# charging-dock-10.net
KiCad netlist of a schematic drawn in EasyEDA Pro
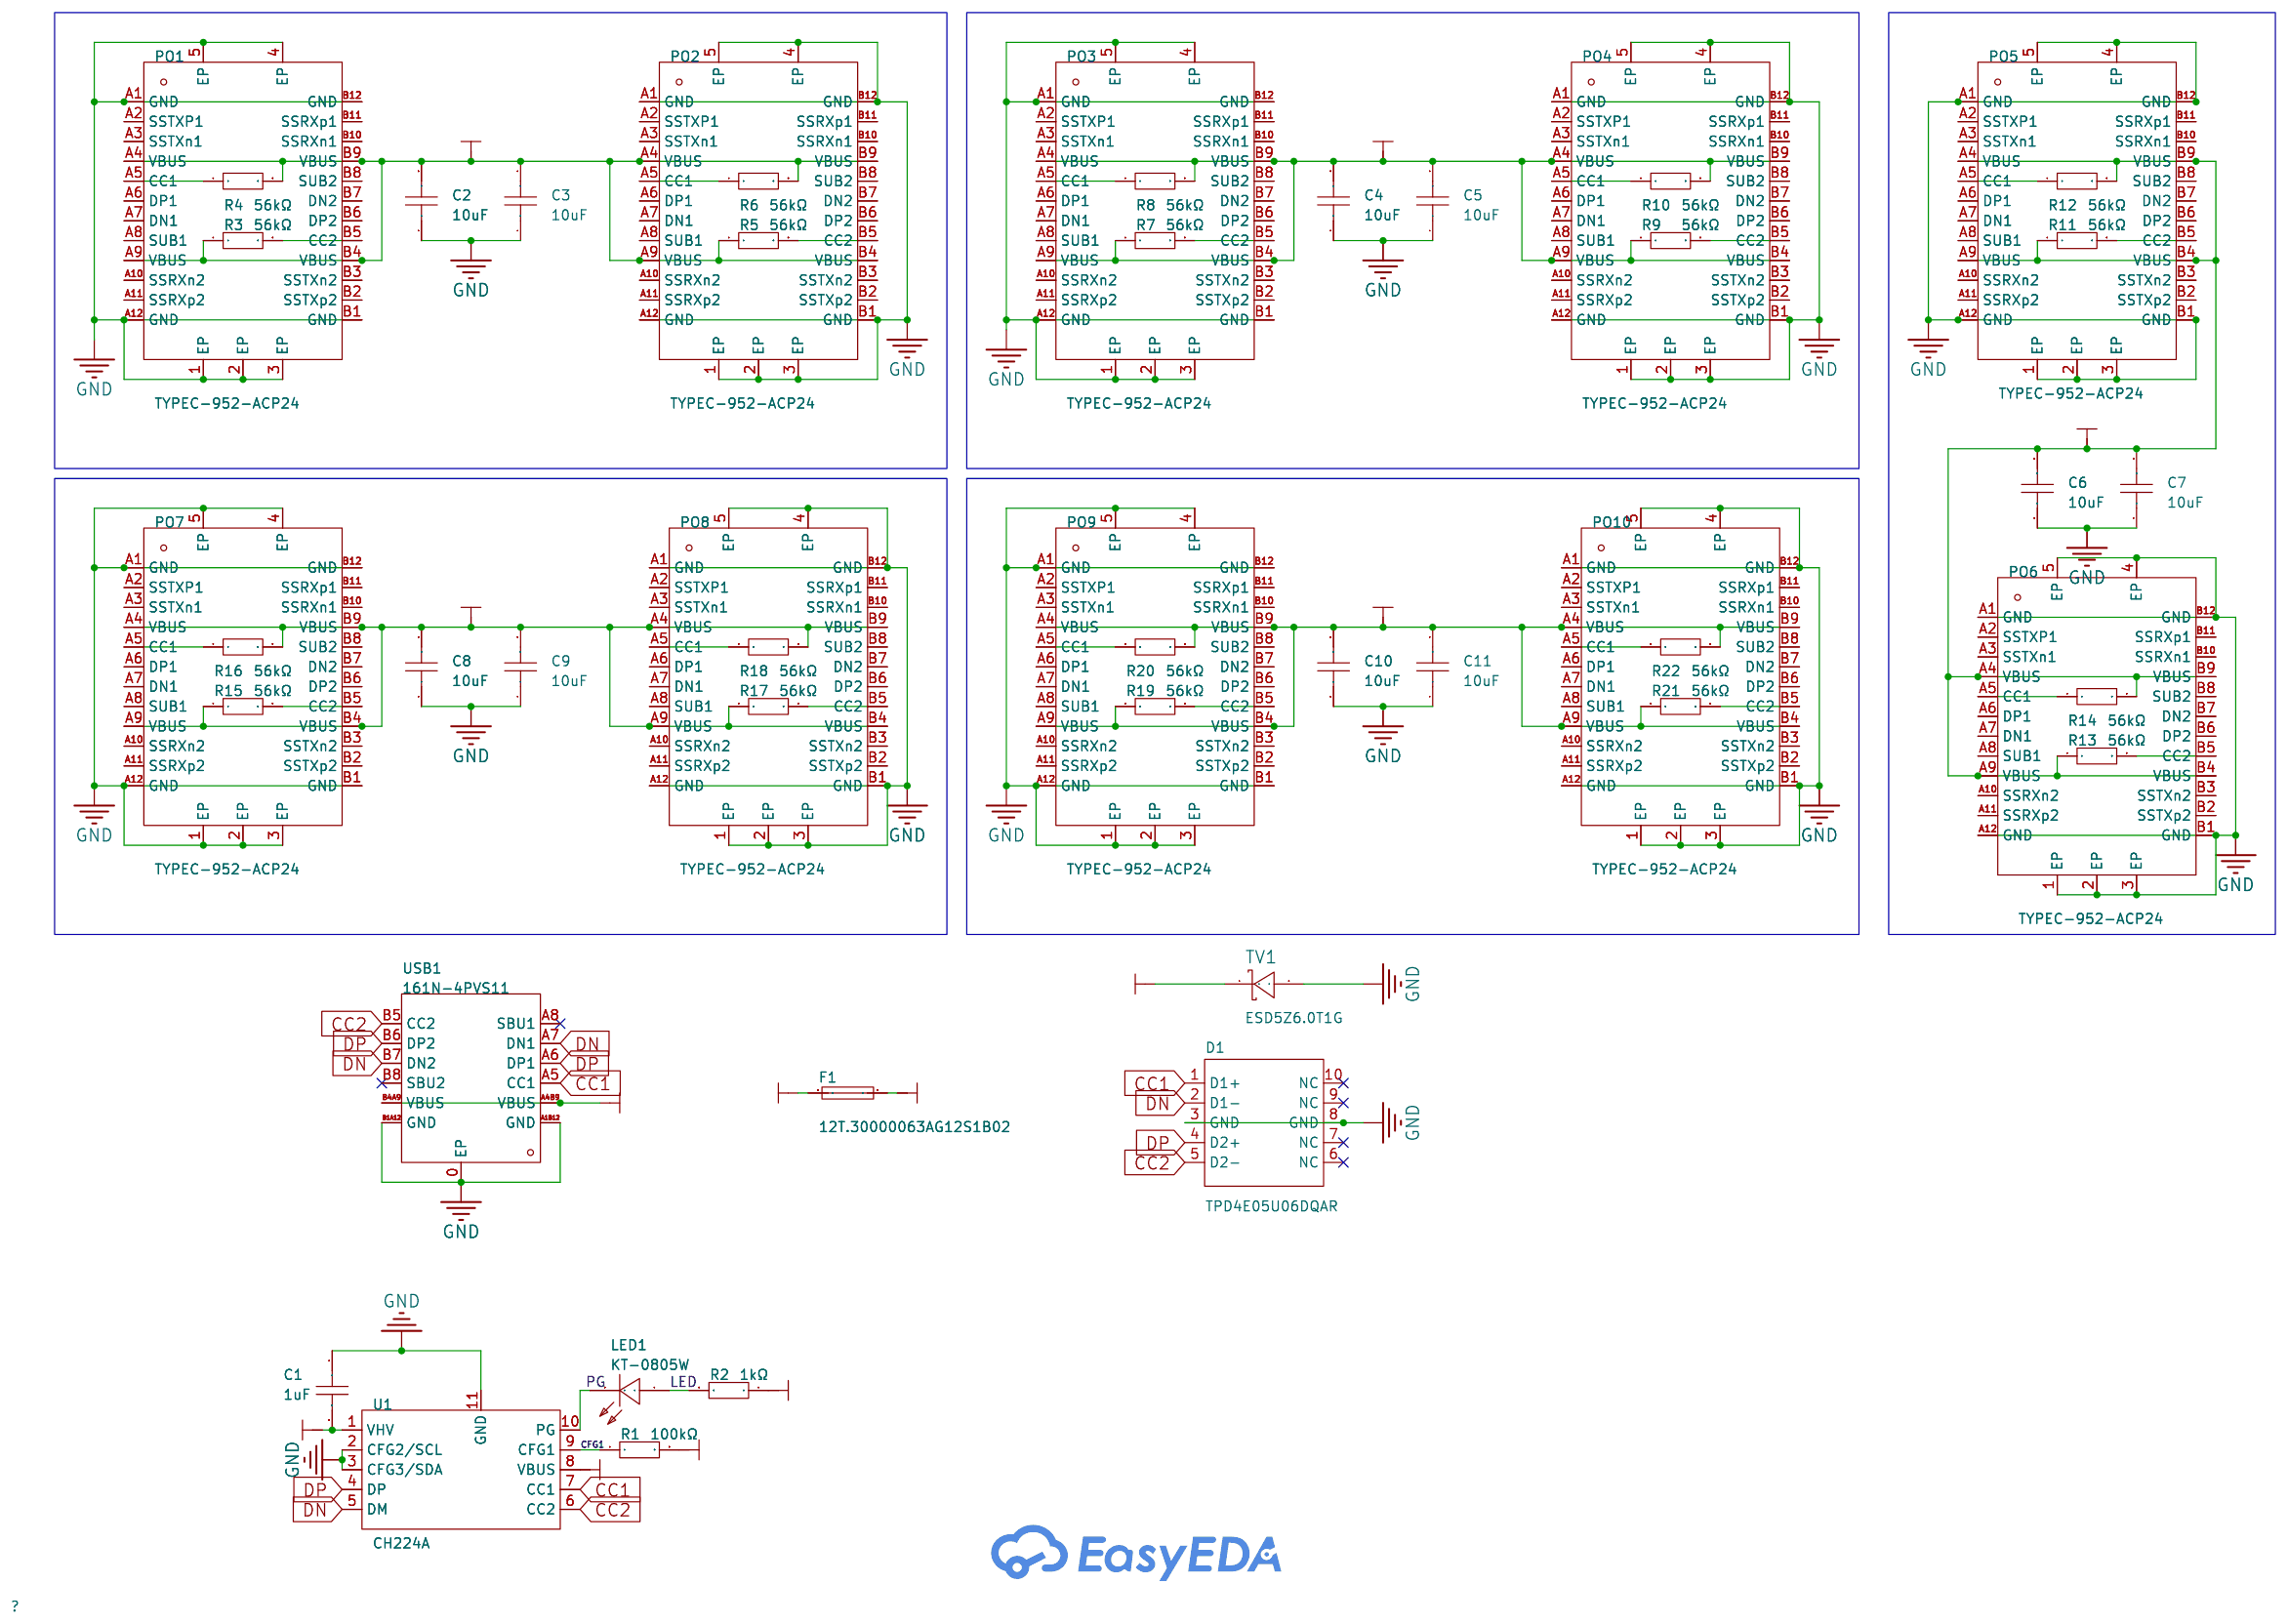
[diagram p0: schematic sheet]

(export (version "E")
  (design (tool "Eeschema 10.0.6"))
  (components
    (comp (ref "C1")
      (value "1uF")
      (footprint "easyedapro:C0603")
      (fields
        (field (name "Manufacturer Part") "CL10A105KB8NNNC")
        (field (name "Manufacturer") "SAMSUNG(三星)")
      )
      (libsource (lib "easyedapro") (part "CL10A105KB8NNNC"))
    )
    (comp (ref "C2")
      (value "10uF")
      (footprint "easyedapro:C0805")
      (fields
        (field (name "Manufacturer Part") "CL21A106KAYNNNE")
        (field (name "Manufacturer") "SAMSUNG(三星)")
      )
      (libsource (lib "easyedapro") (part "CL21A106KAYNNNE"))
    )
    (comp (ref "C3")
      (value "10uF")
      (footprint "easyedapro:C0805")
      (fields
        (field (name "Manufacturer Part") "CL21A106KAYNNNE")
        (field (name "Manufacturer") "SAMSUNG(三星)")
      )
      (libsource (lib "easyedapro") (part "CL21A106KAYNNNE"))
    )
    (comp (ref "C4")
      (value "10uF")
      (footprint "easyedapro:C0805")
      (fields
        (field (name "Manufacturer Part") "CL21A106KAYNNNE")
        (field (name "Manufacturer") "SAMSUNG(三星)")
      )
      (libsource (lib "easyedapro") (part "CL21A106KAYNNNE"))
    )
    (comp (ref "C5")
      (value "10uF")
      (footprint "easyedapro:C0805")
      (fields
        (field (name "Manufacturer Part") "CL21A106KAYNNNE")
        (field (name "Manufacturer") "SAMSUNG(三星)")
      )
      (libsource (lib "easyedapro") (part "CL21A106KAYNNNE"))
    )
    (comp (ref "C6")
      (value "10uF")
      (footprint "easyedapro:C0805")
      (fields
        (field (name "Manufacturer Part") "CL21A106KAYNNNE")
        (field (name "Manufacturer") "SAMSUNG(三星)")
      )
      (libsource (lib "easyedapro") (part "CL21A106KAYNNNE"))
    )
    (comp (ref "C7")
      (value "10uF")
      (footprint "easyedapro:C0805")
      (fields
        (field (name "Manufacturer Part") "CL21A106KAYNNNE")
        (field (name "Manufacturer") "SAMSUNG(三星)")
      )
      (libsource (lib "easyedapro") (part "CL21A106KAYNNNE"))
    )
    (comp (ref "C8")
      (value "10uF")
      (footprint "easyedapro:C0805")
      (fields
        (field (name "Manufacturer Part") "CL21A106KAYNNNE")
        (field (name "Manufacturer") "SAMSUNG(三星)")
      )
      (libsource (lib "easyedapro") (part "CL21A106KAYNNNE"))
    )
    (comp (ref "C9")
      (value "10uF")
      (footprint "easyedapro:C0805")
      (fields
        (field (name "Manufacturer Part") "CL21A106KAYNNNE")
        (field (name "Manufacturer") "SAMSUNG(三星)")
      )
      (libsource (lib "easyedapro") (part "CL21A106KAYNNNE"))
    )
    (comp (ref "C10")
      (value "10uF")
      (footprint "easyedapro:C0805")
      (fields
        (field (name "Manufacturer Part") "CL21A106KAYNNNE")
        (field (name "Manufacturer") "SAMSUNG(三星)")
      )
      (libsource (lib "easyedapro") (part "CL21A106KAYNNNE"))
    )
    (comp (ref "C11")
      (value "10uF")
      (footprint "easyedapro:C0805")
      (fields
        (field (name "Manufacturer Part") "CL21A106KAYNNNE")
        (field (name "Manufacturer") "SAMSUNG(三星)")
      )
      (libsource (lib "easyedapro") (part "CL21A106KAYNNNE"))
    )
    (comp (ref "D1")
      (value "TPD4E05U06DQAR")
      (footprint "easyedapro:USON-10_L2.5-W1.0-P0.50-BL")
      (fields (field (name "Manufacturer") "TI(德州仪器)"))
      (libsource (lib "easyedapro") (part "TPD4E05U06DQAR_C138714"))
    )
    (comp (ref "F1")
      (value "12T.30000063AG12S1B02")
      (footprint "easyedapro:F1206")
      (fields (field (name "Manufacturer") "xcfuse(旭程)"))
      (libsource (lib "easyedapro") (part "3A 63V"))
    )
    (comp (ref "LED1")
      (value "KT-0805W")
      (footprint "easyedapro:LED0805-R-RD")
      (fields (field (name "Manufacturer") "KENTO"))
      (libsource (lib "easyedapro") (part "whiteLEDSMD"))
    )
    (comp (ref "PO1")
      (value "TYPEC-952-ACP24")
      (footprint "easyedapro:USB-C-SMD_TYPEC-952-ACP24-OPENPAW")
      (fields (field (name "Manufacturer") "XUNPU(讯普)"))
      (libsource (lib "easyedapro") (part "TYPEC-952-ACP24"))
    )
    (comp (ref "PO2")
      (value "TYPEC-952-ACP24")
      (footprint "easyedapro:USB-C-SMD_TYPEC-952-ACP24-OPENPAW")
      (fields (field (name "Manufacturer") "XUNPU(讯普)"))
      (libsource (lib "easyedapro") (part "TYPEC-952-ACP24"))
    )
    (comp (ref "PO3")
      (value "TYPEC-952-ACP24")
      (footprint "easyedapro:USB-C-SMD_TYPEC-952-ACP24-OPENPAW")
      (fields (field (name "Manufacturer") "XUNPU(讯普)"))
      (libsource (lib "easyedapro") (part "TYPEC-952-ACP24"))
    )
    (comp (ref "PO4")
      (value "TYPEC-952-ACP24")
      (footprint "easyedapro:USB-C-SMD_TYPEC-952-ACP24-OPENPAW")
      (fields (field (name "Manufacturer") "XUNPU(讯普)"))
      (libsource (lib "easyedapro") (part "TYPEC-952-ACP24"))
    )
    (comp (ref "PO5")
      (value "TYPEC-952-ACP24")
      (footprint "easyedapro:USB-C-SMD_TYPEC-952-ACP24-OPENPAW")
      (fields (field (name "Manufacturer") "XUNPU(讯普)"))
      (libsource (lib "easyedapro") (part "TYPEC-952-ACP24"))
    )
    (comp (ref "PO6")
      (value "TYPEC-952-ACP24")
      (footprint "easyedapro:USB-C-SMD_TYPEC-952-ACP24-OPENPAW")
      (fields (field (name "Manufacturer") "XUNPU(讯普)"))
      (libsource (lib "easyedapro") (part "TYPEC-952-ACP24"))
    )
    (comp (ref "PO7")
      (value "TYPEC-952-ACP24")
      (footprint "easyedapro:USB-C-SMD_TYPEC-952-ACP24-OPENPAW")
      (fields (field (name "Manufacturer") "XUNPU(讯普)"))
      (libsource (lib "easyedapro") (part "TYPEC-952-ACP24"))
    )
    (comp (ref "PO8")
      (value "TYPEC-952-ACP24")
      (footprint "easyedapro:USB-C-SMD_TYPEC-952-ACP24-OPENPAW")
      (fields (field (name "Manufacturer") "XUNPU(讯普)"))
      (libsource (lib "easyedapro") (part "TYPEC-952-ACP24"))
    )
    (comp (ref "PO9")
      (value "TYPEC-952-ACP24")
      (footprint "easyedapro:USB-C-SMD_TYPEC-952-ACP24-OPENPAW")
      (fields (field (name "Manufacturer") "XUNPU(讯普)"))
      (libsource (lib "easyedapro") (part "TYPEC-952-ACP24"))
    )
    (comp (ref "PO10")
      (value "TYPEC-952-ACP24")
      (footprint "easyedapro:USB-C-SMD_TYPEC-952-ACP24-OPENPAW")
      (fields (field (name "Manufacturer") "XUNPU(讯普)"))
      (libsource (lib "easyedapro") (part "TYPEC-952-ACP24"))
    )
    (comp (ref "R1")
      (value "100kΩ")
      (footprint "easyedapro:R0603")
      (fields
        (field (name "Manufacturer Part") "0603WAF1003T5E")
        (field (name "Manufacturer") "UNI-ROYAL(厚声)")
      )
      (libsource (lib "easyedapro") (part "0603WAF1001T5E"))
    )
    (comp (ref "R2")
      (value "1kΩ")
      (footprint "easyedapro:R0603")
      (fields
        (field (name "Manufacturer Part") "0603WAF1001T5E")
        (field (name "Manufacturer") "UNI-ROYAL(厚声)")
      )
      (libsource (lib "easyedapro") (part "0603WAF1001T5E"))
    )
    (comp (ref "R3")
      (value "56kΩ")
      (footprint "easyedapro:R0603")
      (fields
        (field (name "Manufacturer Part") "0603WAF5602T5E")
        (field (name "Manufacturer") "UNI-ROYAL(厚声)")
      )
      (libsource (lib "easyedapro") (part "0603WAF1001T5E"))
    )
    (comp (ref "R4")
      (value "56kΩ")
      (footprint "easyedapro:R0603")
      (fields
        (field (name "Manufacturer Part") "0603WAF5602T5E")
        (field (name "Manufacturer") "UNI-ROYAL(厚声)")
      )
      (libsource (lib "easyedapro") (part "0603WAF1001T5E"))
    )
    (comp (ref "R5")
      (value "56kΩ")
      (footprint "easyedapro:R0603")
      (fields
        (field (name "Manufacturer Part") "0603WAF5602T5E")
        (field (name "Manufacturer") "UNI-ROYAL(厚声)")
      )
      (libsource (lib "easyedapro") (part "0603WAF1001T5E"))
    )
    (comp (ref "R6")
      (value "56kΩ")
      (footprint "easyedapro:R0603")
      (fields
        (field (name "Manufacturer Part") "0603WAF5602T5E")
        (field (name "Manufacturer") "UNI-ROYAL(厚声)")
      )
      (libsource (lib "easyedapro") (part "0603WAF1001T5E"))
    )
    (comp (ref "R7")
      (value "56kΩ")
      (footprint "easyedapro:R0603")
      (fields
        (field (name "Manufacturer Part") "0603WAF5602T5E")
        (field (name "Manufacturer") "UNI-ROYAL(厚声)")
      )
      (libsource (lib "easyedapro") (part "0603WAF1001T5E"))
    )
    (comp (ref "R8")
      (value "56kΩ")
      (footprint "easyedapro:R0603")
      (fields
        (field (name "Manufacturer Part") "0603WAF5602T5E")
        (field (name "Manufacturer") "UNI-ROYAL(厚声)")
      )
      (libsource (lib "easyedapro") (part "0603WAF1001T5E"))
    )
    (comp (ref "R9")
      (value "56kΩ")
      (footprint "easyedapro:R0603")
      (fields
        (field (name "Manufacturer Part") "0603WAF5602T5E")
        (field (name "Manufacturer") "UNI-ROYAL(厚声)")
      )
      (libsource (lib "easyedapro") (part "0603WAF1001T5E"))
    )
    (comp (ref "R10")
      (value "56kΩ")
      (footprint "easyedapro:R0603")
      (fields
        (field (name "Manufacturer Part") "0603WAF5602T5E")
        (field (name "Manufacturer") "UNI-ROYAL(厚声)")
      )
      (libsource (lib "easyedapro") (part "0603WAF1001T5E"))
    )
    (comp (ref "R11")
      (value "56kΩ")
      (footprint "easyedapro:R0603")
      (fields
        (field (name "Manufacturer Part") "0603WAF5602T5E")
        (field (name "Manufacturer") "UNI-ROYAL(厚声)")
      )
      (libsource (lib "easyedapro") (part "0603WAF1001T5E"))
    )
    (comp (ref "R12")
      (value "56kΩ")
      (footprint "easyedapro:R0603")
      (fields
        (field (name "Manufacturer Part") "0603WAF5602T5E")
        (field (name "Manufacturer") "UNI-ROYAL(厚声)")
      )
      (libsource (lib "easyedapro") (part "0603WAF1001T5E"))
    )
    (comp (ref "R13")
      (value "56kΩ")
      (footprint "easyedapro:R0603")
      (fields
        (field (name "Manufacturer Part") "0603WAF5602T5E")
        (field (name "Manufacturer") "UNI-ROYAL(厚声)")
      )
      (libsource (lib "easyedapro") (part "0603WAF1001T5E"))
    )
    (comp (ref "R14")
      (value "56kΩ")
      (footprint "easyedapro:R0603")
      (fields
        (field (name "Manufacturer Part") "0603WAF5602T5E")
        (field (name "Manufacturer") "UNI-ROYAL(厚声)")
      )
      (libsource (lib "easyedapro") (part "0603WAF1001T5E"))
    )
    (comp (ref "R15")
      (value "56kΩ")
      (footprint "easyedapro:R0603")
      (fields
        (field (name "Manufacturer Part") "0603WAF5602T5E")
        (field (name "Manufacturer") "UNI-ROYAL(厚声)")
      )
      (libsource (lib "easyedapro") (part "0603WAF1001T5E"))
    )
    (comp (ref "R16")
      (value "56kΩ")
      (footprint "easyedapro:R0603")
      (fields
        (field (name "Manufacturer Part") "0603WAF5602T5E")
        (field (name "Manufacturer") "UNI-ROYAL(厚声)")
      )
      (libsource (lib "easyedapro") (part "0603WAF1001T5E"))
    )
    (comp (ref "R17")
      (value "56kΩ")
      (footprint "easyedapro:R0603")
      (fields
        (field (name "Manufacturer Part") "0603WAF5602T5E")
        (field (name "Manufacturer") "UNI-ROYAL(厚声)")
      )
      (libsource (lib "easyedapro") (part "0603WAF1001T5E"))
    )
    (comp (ref "R18")
      (value "56kΩ")
      (footprint "easyedapro:R0603")
      (fields
        (field (name "Manufacturer Part") "0603WAF5602T5E")
        (field (name "Manufacturer") "UNI-ROYAL(厚声)")
      )
      (libsource (lib "easyedapro") (part "0603WAF1001T5E"))
    )
    (comp (ref "R19")
      (value "56kΩ")
      (footprint "easyedapro:R0603")
      (fields
        (field (name "Manufacturer Part") "0603WAF5602T5E")
        (field (name "Manufacturer") "UNI-ROYAL(厚声)")
      )
      (libsource (lib "easyedapro") (part "0603WAF1001T5E"))
    )
    (comp (ref "R20")
      (value "56kΩ")
      (footprint "easyedapro:R0603")
      (fields
        (field (name "Manufacturer Part") "0603WAF5602T5E")
        (field (name "Manufacturer") "UNI-ROYAL(厚声)")
      )
      (libsource (lib "easyedapro") (part "0603WAF1001T5E"))
    )
    (comp (ref "R21")
      (value "56kΩ")
      (footprint "easyedapro:R0603")
      (fields
        (field (name "Manufacturer Part") "0603WAF5602T5E")
        (field (name "Manufacturer") "UNI-ROYAL(厚声)")
      )
      (libsource (lib "easyedapro") (part "0603WAF1001T5E"))
    )
    (comp (ref "R22")
      (value "56kΩ")
      (footprint "easyedapro:R0603")
      (fields
        (field (name "Manufacturer Part") "0603WAF5602T5E")
        (field (name "Manufacturer") "UNI-ROYAL(厚声)")
      )
      (libsource (lib "easyedapro") (part "0603WAF1001T5E"))
    )
    (comp (ref "TV1")
      (value "ESD5Z6.0T1G")
      (footprint "easyedapro:SOD-523F_L1.2-W0.8-LS1.7-RD")
      (fields (field (name "Manufacturer") "onsemi(安森美)"))
      (libsource (lib "easyedapro") (part "ESD5Z6.0T1G"))
    )
    (comp (ref "U1")
      (value "CH224A")
      (footprint "easyedapro:ESSOP-10_L4.9-W3.9-P1.0-LS6.0-TL-EP")
      (fields (field (name "Manufacturer") "WCH(南京沁恒)"))
      (libsource (lib "easyedapro") (part "CH224A"))
    )
    (comp (ref "USB1")
      (value "161N-4PVS11")
      (footprint "easyedapro:USB-C-SMD_HANELECTRICITY_161N-4XVS11")
      (fields (field (name "Manufacturer") "HanElectricity(瀚源)"))
      (libsource (lib "easyedapro") (part "161N-4PVS11"))
    )
  )
  (nets
    (net (code "1") (name "/CFG1") (class "Default")
      (node (ref "R1") (pin "1") (pinfunction "1_1") (pintype "input"))
      (node (ref "U1") (pin "9") (pinfunction "CFG1_9") (pintype "unspecified"))
    )
    (net (code "2") (name "/LED") (class "Default")
      (node (ref "LED1") (pin "1") (pinfunction "A_1") (pintype "unspecified"))
      (node (ref "R2") (pin "2") (pinfunction "2_2") (pintype "input"))
    )
    (net (code "3") (name "/PG") (class "Default")
      (node (ref "LED1") (pin "2") (pinfunction "K_2") (pintype "unspecified"))
      (node (ref "U1") (pin "10") (pinfunction "PG_10") (pintype "unspecified"))
    )
    (net (code "4") (name "CC1") (class "Default")
      (node (ref "D1") (pin "1") (pinfunction "D1+_1") (pintype "unspecified"))
      (node (ref "U1") (pin "7") (pinfunction "CC1_7") (pintype "unspecified"))
      (node (ref "USB1") (pin "A5") (pinfunction "CC1_A5") (pintype "unspecified"))
    )
    (net (code "5") (name "CC2") (class "Default")
      (node (ref "D1") (pin "5") (pinfunction "D2-_5") (pintype "unspecified"))
      (node (ref "U1") (pin "6") (pinfunction "CC2_6") (pintype "unspecified"))
      (node (ref "USB1") (pin "B5") (pinfunction "CC2_B5") (pintype "unspecified"))
    )
    (net (code "6") (name "DN") (class "Default")
      (node (ref "D1") (pin "2") (pinfunction "D1-_2") (pintype "unspecified"))
      (node (ref "U1") (pin "5") (pinfunction "DM_5") (pintype "unspecified"))
      (node (ref "USB1") (pin "A7") (pinfunction "DN1_A7") (pintype "unspecified"))
      (node (ref "USB1") (pin "B7") (pinfunction "DN2_B7") (pintype "unspecified"))
    )
    (net (code "7") (name "DP") (class "Default")
      (node (ref "D1") (pin "4") (pinfunction "D2+_4") (pintype "unspecified"))
      (node (ref "U1") (pin "4") (pinfunction "DP_4") (pintype "unspecified"))
      (node (ref "USB1") (pin "A6") (pinfunction "DP1_A6") (pintype "unspecified"))
      (node (ref "USB1") (pin "B6") (pinfunction "DP2_B6") (pintype "unspecified"))
    )
    (net (code "8") (name "GND") (class "Default")
      (node (ref "C1") (pin "1") (pinfunction "1_1") (pintype "unspecified"))
      (node (ref "C10") (pin "1") (pinfunction "1_1") (pintype "unspecified"))
      (node (ref "C11") (pin "1") (pinfunction "1_1") (pintype "unspecified"))
      (node (ref "C2") (pin "1") (pinfunction "1_1") (pintype "unspecified"))
      (node (ref "C3") (pin "1") (pinfunction "1_1") (pintype "unspecified"))
      (node (ref "C4") (pin "1") (pinfunction "1_1") (pintype "unspecified"))
      (node (ref "C5") (pin "1") (pinfunction "1_1") (pintype "unspecified"))
      (node (ref "C6") (pin "1") (pinfunction "1_1") (pintype "unspecified"))
      (node (ref "C7") (pin "1") (pinfunction "1_1") (pintype "unspecified"))
      (node (ref "C8") (pin "1") (pinfunction "1_1") (pintype "unspecified"))
      (node (ref "C9") (pin "1") (pinfunction "1_1") (pintype "unspecified"))
      (node (ref "D1") (pin "3") (pinfunction "GND_3") (pintype "unspecified"))
      (node (ref "D1") (pin "8") (pinfunction "GND_8") (pintype "unspecified"))
      (node (ref "PO1") (pin "1") (pinfunction "EP_1") (pintype "input"))
      (node (ref "PO1") (pin "2") (pinfunction "EP_2") (pintype "input"))
      (node (ref "PO1") (pin "3") (pinfunction "EP_3") (pintype "input"))
      (node (ref "PO1") (pin "4") (pinfunction "EP_4") (pintype "input"))
      (node (ref "PO1") (pin "5") (pinfunction "EP_5") (pintype "input"))
      (node (ref "PO1") (pin "A1") (pinfunction "GND_A1") (pintype "input"))
      (node (ref "PO1") (pin "A12") (pinfunction "GND_A12") (pintype "input"))
      (node (ref "PO1") (pin "B1") (pinfunction "GND_B1") (pintype "input"))
      (node (ref "PO1") (pin "B12") (pinfunction "GND_B12") (pintype "input"))
      (node (ref "PO10") (pin "1") (pinfunction "EP_1") (pintype "input"))
      (node (ref "PO10") (pin "2") (pinfunction "EP_2") (pintype "input"))
      (node (ref "PO10") (pin "3") (pinfunction "EP_3") (pintype "input"))
      (node (ref "PO10") (pin "4") (pinfunction "EP_4") (pintype "input"))
      (node (ref "PO10") (pin "5") (pinfunction "EP_5") (pintype "input"))
      (node (ref "PO10") (pin "A1") (pinfunction "GND_A1") (pintype "input"))
      (node (ref "PO10") (pin "A12") (pinfunction "GND_A12") (pintype "input"))
      (node (ref "PO10") (pin "B1") (pinfunction "GND_B1") (pintype "input"))
      (node (ref "PO10") (pin "B12") (pinfunction "GND_B12") (pintype "input"))
      (node (ref "PO2") (pin "1") (pinfunction "EP_1") (pintype "input"))
      (node (ref "PO2") (pin "2") (pinfunction "EP_2") (pintype "input"))
      (node (ref "PO2") (pin "3") (pinfunction "EP_3") (pintype "input"))
      (node (ref "PO2") (pin "4") (pinfunction "EP_4") (pintype "input"))
      (node (ref "PO2") (pin "5") (pinfunction "EP_5") (pintype "input"))
      (node (ref "PO2") (pin "A1") (pinfunction "GND_A1") (pintype "input"))
      (node (ref "PO2") (pin "A12") (pinfunction "GND_A12") (pintype "input"))
      (node (ref "PO2") (pin "B1") (pinfunction "GND_B1") (pintype "input"))
      (node (ref "PO2") (pin "B12") (pinfunction "GND_B12") (pintype "input"))
      (node (ref "PO3") (pin "1") (pinfunction "EP_1") (pintype "input"))
      (node (ref "PO3") (pin "2") (pinfunction "EP_2") (pintype "input"))
      (node (ref "PO3") (pin "3") (pinfunction "EP_3") (pintype "input"))
      (node (ref "PO3") (pin "4") (pinfunction "EP_4") (pintype "input"))
      (node (ref "PO3") (pin "5") (pinfunction "EP_5") (pintype "input"))
      (node (ref "PO3") (pin "A1") (pinfunction "GND_A1") (pintype "input"))
      (node (ref "PO3") (pin "A12") (pinfunction "GND_A12") (pintype "input"))
      (node (ref "PO3") (pin "B1") (pinfunction "GND_B1") (pintype "input"))
      (node (ref "PO3") (pin "B12") (pinfunction "GND_B12") (pintype "input"))
      (node (ref "PO4") (pin "1") (pinfunction "EP_1") (pintype "input"))
      (node (ref "PO4") (pin "2") (pinfunction "EP_2") (pintype "input"))
      (node (ref "PO4") (pin "3") (pinfunction "EP_3") (pintype "input"))
      (node (ref "PO4") (pin "4") (pinfunction "EP_4") (pintype "input"))
      (node (ref "PO4") (pin "5") (pinfunction "EP_5") (pintype "input"))
      (node (ref "PO4") (pin "A1") (pinfunction "GND_A1") (pintype "input"))
      (node (ref "PO4") (pin "A12") (pinfunction "GND_A12") (pintype "input"))
      (node (ref "PO4") (pin "B1") (pinfunction "GND_B1") (pintype "input"))
      (node (ref "PO4") (pin "B12") (pinfunction "GND_B12") (pintype "input"))
      (node (ref "PO5") (pin "1") (pinfunction "EP_1") (pintype "input"))
      (node (ref "PO5") (pin "2") (pinfunction "EP_2") (pintype "input"))
      (node (ref "PO5") (pin "3") (pinfunction "EP_3") (pintype "input"))
      (node (ref "PO5") (pin "4") (pinfunction "EP_4") (pintype "input"))
      (node (ref "PO5") (pin "5") (pinfunction "EP_5") (pintype "input"))
      (node (ref "PO5") (pin "A1") (pinfunction "GND_A1") (pintype "input"))
      (node (ref "PO5") (pin "A12") (pinfunction "GND_A12") (pintype "input"))
      (node (ref "PO5") (pin "B1") (pinfunction "GND_B1") (pintype "input"))
      (node (ref "PO5") (pin "B12") (pinfunction "GND_B12") (pintype "input"))
      (node (ref "PO6") (pin "1") (pinfunction "EP_1") (pintype "input"))
      (node (ref "PO6") (pin "2") (pinfunction "EP_2") (pintype "input"))
      (node (ref "PO6") (pin "3") (pinfunction "EP_3") (pintype "input"))
      (node (ref "PO6") (pin "4") (pinfunction "EP_4") (pintype "input"))
      (node (ref "PO6") (pin "5") (pinfunction "EP_5") (pintype "input"))
      (node (ref "PO6") (pin "A1") (pinfunction "GND_A1") (pintype "input"))
      (node (ref "PO6") (pin "A12") (pinfunction "GND_A12") (pintype "input"))
      (node (ref "PO6") (pin "B1") (pinfunction "GND_B1") (pintype "input"))
      (node (ref "PO6") (pin "B12") (pinfunction "GND_B12") (pintype "input"))
      (node (ref "PO7") (pin "1") (pinfunction "EP_1") (pintype "input"))
      (node (ref "PO7") (pin "2") (pinfunction "EP_2") (pintype "input"))
      (node (ref "PO7") (pin "3") (pinfunction "EP_3") (pintype "input"))
      (node (ref "PO7") (pin "4") (pinfunction "EP_4") (pintype "input"))
      (node (ref "PO7") (pin "5") (pinfunction "EP_5") (pintype "input"))
      (node (ref "PO7") (pin "A1") (pinfunction "GND_A1") (pintype "input"))
      (node (ref "PO7") (pin "A12") (pinfunction "GND_A12") (pintype "input"))
      (node (ref "PO7") (pin "B1") (pinfunction "GND_B1") (pintype "input"))
      (node (ref "PO7") (pin "B12") (pinfunction "GND_B12") (pintype "input"))
      (node (ref "PO8") (pin "1") (pinfunction "EP_1") (pintype "input"))
      (node (ref "PO8") (pin "2") (pinfunction "EP_2") (pintype "input"))
      (node (ref "PO8") (pin "3") (pinfunction "EP_3") (pintype "input"))
      (node (ref "PO8") (pin "4") (pinfunction "EP_4") (pintype "input"))
      (node (ref "PO8") (pin "5") (pinfunction "EP_5") (pintype "input"))
      (node (ref "PO8") (pin "A1") (pinfunction "GND_A1") (pintype "input"))
      (node (ref "PO8") (pin "A12") (pinfunction "GND_A12") (pintype "input"))
      (node (ref "PO8") (pin "B1") (pinfunction "GND_B1") (pintype "input"))
      (node (ref "PO8") (pin "B12") (pinfunction "GND_B12") (pintype "input"))
      (node (ref "PO9") (pin "1") (pinfunction "EP_1") (pintype "input"))
      (node (ref "PO9") (pin "2") (pinfunction "EP_2") (pintype "input"))
      (node (ref "PO9") (pin "3") (pinfunction "EP_3") (pintype "input"))
      (node (ref "PO9") (pin "4") (pinfunction "EP_4") (pintype "input"))
      (node (ref "PO9") (pin "5") (pinfunction "EP_5") (pintype "input"))
      (node (ref "PO9") (pin "A1") (pinfunction "GND_A1") (pintype "input"))
      (node (ref "PO9") (pin "A12") (pinfunction "GND_A12") (pintype "input"))
      (node (ref "PO9") (pin "B1") (pinfunction "GND_B1") (pintype "input"))
      (node (ref "PO9") (pin "B12") (pinfunction "GND_B12") (pintype "input"))
      (node (ref "TV1") (pin "2") (pinfunction "A_2") (pintype "input"))
      (node (ref "U1") (pin "11") (pinfunction "GND_11") (pintype "unspecified"))
      (node (ref "U1") (pin "2") (pinfunction "CFG2/SCL_2") (pintype "unspecified"))
      (node (ref "U1") (pin "3") (pinfunction "CFG3/SDA_3") (pintype "unspecified"))
      (node (ref "USB1") (pin "0") (pinfunction "EP_0") (pintype "unspecified"))
      (node (ref "USB1") (pin "A1B12") (pinfunction "GND_A1B12") (pintype "unspecified"))
      (node (ref "USB1") (pin "B1A12") (pinfunction "GND_B1A12") (pintype "unspecified"))
    )
    (net (code "9") (name "Net-(PO1-CC1)") (class "Default")
      (node (ref "PO1") (pin "A5") (pinfunction "CC1_A5") (pintype "input"))
      (node (ref "R4") (pin "1") (pinfunction "1_1") (pintype "input"))
    )
    (net (code "10") (name "Net-(PO1-CC2)") (class "Default")
      (node (ref "PO1") (pin "B5") (pinfunction "CC2_B5") (pintype "input"))
      (node (ref "R3") (pin "2") (pinfunction "2_2") (pintype "input"))
    )
    (net (code "11") (name "Net-(PO2-CC1)") (class "Default")
      (node (ref "PO2") (pin "A5") (pinfunction "CC1_A5") (pintype "input"))
      (node (ref "R6") (pin "1") (pinfunction "1_1") (pintype "input"))
    )
    (net (code "12") (name "Net-(PO2-CC2)") (class "Default")
      (node (ref "PO2") (pin "B5") (pinfunction "CC2_B5") (pintype "input"))
      (node (ref "R5") (pin "2") (pinfunction "2_2") (pintype "input"))
    )
    (net (code "13") (name "Net-(PO3-CC1)") (class "Default")
      (node (ref "PO3") (pin "A5") (pinfunction "CC1_A5") (pintype "input"))
      (node (ref "R8") (pin "1") (pinfunction "1_1") (pintype "input"))
    )
    (net (code "14") (name "Net-(PO3-CC2)") (class "Default")
      (node (ref "PO3") (pin "B5") (pinfunction "CC2_B5") (pintype "input"))
      (node (ref "R7") (pin "2") (pinfunction "2_2") (pintype "input"))
    )
    (net (code "15") (name "Net-(PO4-CC1)") (class "Default")
      (node (ref "PO4") (pin "A5") (pinfunction "CC1_A5") (pintype "input"))
      (node (ref "R10") (pin "1") (pinfunction "1_1") (pintype "input"))
    )
    (net (code "16") (name "Net-(PO4-CC2)") (class "Default")
      (node (ref "PO4") (pin "B5") (pinfunction "CC2_B5") (pintype "input"))
      (node (ref "R9") (pin "2") (pinfunction "2_2") (pintype "input"))
    )
    (net (code "17") (name "Net-(PO5-CC1)") (class "Default")
      (node (ref "PO5") (pin "A5") (pinfunction "CC1_A5") (pintype "input"))
      (node (ref "R12") (pin "1") (pinfunction "1_1") (pintype "input"))
    )
    (net (code "18") (name "Net-(PO5-CC2)") (class "Default")
      (node (ref "PO5") (pin "B5") (pinfunction "CC2_B5") (pintype "input"))
      (node (ref "R11") (pin "2") (pinfunction "2_2") (pintype "input"))
    )
    (net (code "19") (name "Net-(PO6-CC1)") (class "Default")
      (node (ref "PO6") (pin "A5") (pinfunction "CC1_A5") (pintype "input"))
      (node (ref "R14") (pin "1") (pinfunction "1_1") (pintype "input"))
    )
    (net (code "20") (name "Net-(PO6-CC2)") (class "Default")
      (node (ref "PO6") (pin "B5") (pinfunction "CC2_B5") (pintype "input"))
      (node (ref "R13") (pin "2") (pinfunction "2_2") (pintype "input"))
    )
    (net (code "21") (name "Net-(PO7-CC1)") (class "Default")
      (node (ref "PO7") (pin "A5") (pinfunction "CC1_A5") (pintype "input"))
      (node (ref "R16") (pin "1") (pinfunction "1_1") (pintype "input"))
    )
    (net (code "22") (name "Net-(PO7-CC2)") (class "Default")
      (node (ref "PO7") (pin "B5") (pinfunction "CC2_B5") (pintype "input"))
      (node (ref "R15") (pin "2") (pinfunction "2_2") (pintype "input"))
    )
    (net (code "23") (name "Net-(PO8-CC1)") (class "Default")
      (node (ref "PO8") (pin "A5") (pinfunction "CC1_A5") (pintype "input"))
      (node (ref "R18") (pin "1") (pinfunction "1_1") (pintype "input"))
    )
    (net (code "24") (name "Net-(PO8-CC2)") (class "Default")
      (node (ref "PO8") (pin "B5") (pinfunction "CC2_B5") (pintype "input"))
      (node (ref "R17") (pin "2") (pinfunction "2_2") (pintype "input"))
    )
    (net (code "25") (name "Net-(PO9-CC1)") (class "Default")
      (node (ref "PO9") (pin "A5") (pinfunction "CC1_A5") (pintype "input"))
      (node (ref "R20") (pin "1") (pinfunction "1_1") (pintype "input"))
    )
    (net (code "26") (name "Net-(PO9-CC2)") (class "Default")
      (node (ref "PO9") (pin "B5") (pinfunction "CC2_B5") (pintype "input"))
      (node (ref "R19") (pin "2") (pinfunction "2_2") (pintype "input"))
    )
    (net (code "27") (name "Net-(PO10-CC1)") (class "Default")
      (node (ref "PO10") (pin "A5") (pinfunction "CC1_A5") (pintype "input"))
      (node (ref "R22") (pin "1") (pinfunction "1_1") (pintype "input"))
    )
    (net (code "28") (name "Net-(PO10-CC2)") (class "Default")
      (node (ref "PO10") (pin "B5") (pinfunction "CC2_B5") (pintype "input"))
      (node (ref "R21") (pin "2") (pinfunction "2_2") (pintype "input"))
    )
    (net (code "29") (name "PVBUS") (class "Default")
      (node (ref "C1") (pin "2") (pinfunction "2_2") (pintype "unspecified"))
      (node (ref "C10") (pin "2") (pinfunction "2_2") (pintype "unspecified"))
      (node (ref "C11") (pin "2") (pinfunction "2_2") (pintype "unspecified"))
      (node (ref "C2") (pin "2") (pinfunction "2_2") (pintype "unspecified"))
      (node (ref "C3") (pin "2") (pinfunction "2_2") (pintype "unspecified"))
      (node (ref "C4") (pin "2") (pinfunction "2_2") (pintype "unspecified"))
      (node (ref "C5") (pin "2") (pinfunction "2_2") (pintype "unspecified"))
      (node (ref "C6") (pin "2") (pinfunction "2_2") (pintype "unspecified"))
      (node (ref "C7") (pin "2") (pinfunction "2_2") (pintype "unspecified"))
      (node (ref "C8") (pin "2") (pinfunction "2_2") (pintype "unspecified"))
      (node (ref "C9") (pin "2") (pinfunction "2_2") (pintype "unspecified"))
      (node (ref "F1") (pin "1") (pinfunction "1_1") (pintype "unspecified"))
      (node (ref "PO1") (pin "A4") (pinfunction "VBUS_A4") (pintype "input"))
      (node (ref "PO1") (pin "A9") (pinfunction "VBUS_A9") (pintype "input"))
      (node (ref "PO1") (pin "B4") (pinfunction "VBUS_B4") (pintype "input"))
      (node (ref "PO1") (pin "B9") (pinfunction "VBUS_B9") (pintype "input"))
      (node (ref "PO10") (pin "A4") (pinfunction "VBUS_A4") (pintype "input"))
      (node (ref "PO10") (pin "A9") (pinfunction "VBUS_A9") (pintype "input"))
      (node (ref "PO10") (pin "B4") (pinfunction "VBUS_B4") (pintype "input"))
      (node (ref "PO10") (pin "B9") (pinfunction "VBUS_B9") (pintype "input"))
      (node (ref "PO2") (pin "A4") (pinfunction "VBUS_A4") (pintype "input"))
      (node (ref "PO2") (pin "A9") (pinfunction "VBUS_A9") (pintype "input"))
      (node (ref "PO2") (pin "B4") (pinfunction "VBUS_B4") (pintype "input"))
      (node (ref "PO2") (pin "B9") (pinfunction "VBUS_B9") (pintype "input"))
      (node (ref "PO3") (pin "A4") (pinfunction "VBUS_A4") (pintype "input"))
      (node (ref "PO3") (pin "A9") (pinfunction "VBUS_A9") (pintype "input"))
      (node (ref "PO3") (pin "B4") (pinfunction "VBUS_B4") (pintype "input"))
      (node (ref "PO3") (pin "B9") (pinfunction "VBUS_B9") (pintype "input"))
      (node (ref "PO4") (pin "A4") (pinfunction "VBUS_A4") (pintype "input"))
      (node (ref "PO4") (pin "A9") (pinfunction "VBUS_A9") (pintype "input"))
      (node (ref "PO4") (pin "B4") (pinfunction "VBUS_B4") (pintype "input"))
      (node (ref "PO4") (pin "B9") (pinfunction "VBUS_B9") (pintype "input"))
      (node (ref "PO5") (pin "A4") (pinfunction "VBUS_A4") (pintype "input"))
      (node (ref "PO5") (pin "A9") (pinfunction "VBUS_A9") (pintype "input"))
      (node (ref "PO5") (pin "B4") (pinfunction "VBUS_B4") (pintype "input"))
      (node (ref "PO5") (pin "B9") (pinfunction "VBUS_B9") (pintype "input"))
      (node (ref "PO6") (pin "A4") (pinfunction "VBUS_A4") (pintype "input"))
      (node (ref "PO6") (pin "A9") (pinfunction "VBUS_A9") (pintype "input"))
      (node (ref "PO6") (pin "B4") (pinfunction "VBUS_B4") (pintype "input"))
      (node (ref "PO6") (pin "B9") (pinfunction "VBUS_B9") (pintype "input"))
      (node (ref "PO7") (pin "A4") (pinfunction "VBUS_A4") (pintype "input"))
      (node (ref "PO7") (pin "A9") (pinfunction "VBUS_A9") (pintype "input"))
      (node (ref "PO7") (pin "B4") (pinfunction "VBUS_B4") (pintype "input"))
      (node (ref "PO7") (pin "B9") (pinfunction "VBUS_B9") (pintype "input"))
      (node (ref "PO8") (pin "A4") (pinfunction "VBUS_A4") (pintype "input"))
      (node (ref "PO8") (pin "A9") (pinfunction "VBUS_A9") (pintype "input"))
      (node (ref "PO8") (pin "B4") (pinfunction "VBUS_B4") (pintype "input"))
      (node (ref "PO8") (pin "B9") (pinfunction "VBUS_B9") (pintype "input"))
      (node (ref "PO9") (pin "A4") (pinfunction "VBUS_A4") (pintype "input"))
      (node (ref "PO9") (pin "A9") (pinfunction "VBUS_A9") (pintype "input"))
      (node (ref "PO9") (pin "B4") (pinfunction "VBUS_B4") (pintype "input"))
      (node (ref "PO9") (pin "B9") (pinfunction "VBUS_B9") (pintype "input"))
      (node (ref "R1") (pin "2") (pinfunction "2_2") (pintype "input"))
      (node (ref "R10") (pin "2") (pinfunction "2_2") (pintype "input"))
      (node (ref "R11") (pin "1") (pinfunction "1_1") (pintype "input"))
      (node (ref "R12") (pin "2") (pinfunction "2_2") (pintype "input"))
      (node (ref "R13") (pin "1") (pinfunction "1_1") (pintype "input"))
      (node (ref "R14") (pin "2") (pinfunction "2_2") (pintype "input"))
      (node (ref "R15") (pin "1") (pinfunction "1_1") (pintype "input"))
      (node (ref "R16") (pin "2") (pinfunction "2_2") (pintype "input"))
      (node (ref "R17") (pin "1") (pinfunction "1_1") (pintype "input"))
      (node (ref "R18") (pin "2") (pinfunction "2_2") (pintype "input"))
      (node (ref "R19") (pin "1") (pinfunction "1_1") (pintype "input"))
      (node (ref "R2") (pin "1") (pinfunction "1_1") (pintype "input"))
      (node (ref "R20") (pin "2") (pinfunction "2_2") (pintype "input"))
      (node (ref "R21") (pin "1") (pinfunction "1_1") (pintype "input"))
      (node (ref "R22") (pin "2") (pinfunction "2_2") (pintype "input"))
      (node (ref "R3") (pin "1") (pinfunction "1_1") (pintype "input"))
      (node (ref "R4") (pin "2") (pinfunction "2_2") (pintype "input"))
      (node (ref "R5") (pin "1") (pinfunction "1_1") (pintype "input"))
      (node (ref "R6") (pin "2") (pinfunction "2_2") (pintype "input"))
      (node (ref "R7") (pin "1") (pinfunction "1_1") (pintype "input"))
      (node (ref "R8") (pin "2") (pinfunction "2_2") (pintype "input"))
      (node (ref "R9") (pin "1") (pinfunction "1_1") (pintype "input"))
      (node (ref "TV1") (pin "1") (pinfunction "K_1") (pintype "input"))
      (node (ref "U1") (pin "1") (pinfunction "VHV_1") (pintype "unspecified"))
      (node (ref "U1") (pin "8") (pinfunction "VBUS_8") (pintype "unspecified"))
    )
    (net (code "30") (name "VBUS") (class "Default")
      (node (ref "F1") (pin "2") (pinfunction "2_2") (pintype "unspecified"))
      (node (ref "USB1") (pin "A4B9") (pinfunction "VBUS_A4B9") (pintype "unspecified"))
      (node (ref "USB1") (pin "B4A9") (pinfunction "VBUS_B4A9") (pintype "unspecified"))
    )
    (net (code "31") (name "unconnected-(D1-NC-Pad6)") (class "Default")
      (node (ref "D1") (pin "6") (pinfunction "NC_6") (pintype "unspecified+no_connect"))
    )
    (net (code "32") (name "unconnected-(D1-NC-Pad7)") (class "Default")
      (node (ref "D1") (pin "7") (pinfunction "NC_7") (pintype "unspecified+no_connect"))
    )
    (net (code "33") (name "unconnected-(D1-NC-Pad9)") (class "Default")
      (node (ref "D1") (pin "9") (pinfunction "NC_9") (pintype "unspecified+no_connect"))
    )
    (net (code "34") (name "unconnected-(D1-NC-Pad10)") (class "Default")
      (node (ref "D1") (pin "10") (pinfunction "NC_10") (pintype "unspecified+no_connect"))
    )
    (net (code "35") (name "unconnected-(PO1-DN1-PadA7)") (class "Default")
      (node (ref "PO1") (pin "A7") (pinfunction "DN1_A7") (pintype "input"))
    )
    (net (code "36") (name "unconnected-(PO1-DN2-PadB7)") (class "Default")
      (node (ref "PO1") (pin "B7") (pinfunction "DN2_B7") (pintype "input"))
    )
    (net (code "37") (name "unconnected-(PO1-DP1-PadA6)") (class "Default")
      (node (ref "PO1") (pin "A6") (pinfunction "DP1_A6") (pintype "input"))
    )
    (net (code "38") (name "unconnected-(PO1-DP2-PadB6)") (class "Default")
      (node (ref "PO1") (pin "B6") (pinfunction "DP2_B6") (pintype "input"))
    )
    (net (code "39") (name "unconnected-(PO1-SSRXn1-PadB10)") (class "Default")
      (node (ref "PO1") (pin "B10") (pinfunction "SSRXn1_B10") (pintype "input"))
    )
    (net (code "40") (name "unconnected-(PO1-SSRXn2-PadA10)") (class "Default")
      (node (ref "PO1") (pin "A10") (pinfunction "SSRXn2_A10") (pintype "input"))
    )
    (net (code "41") (name "unconnected-(PO1-SSRXp1-PadB11)") (class "Default")
      (node (ref "PO1") (pin "B11") (pinfunction "SSRXp1_B11") (pintype "input"))
    )
    (net (code "42") (name "unconnected-(PO1-SSRXp2-PadA11)") (class "Default")
      (node (ref "PO1") (pin "A11") (pinfunction "SSRXp2_A11") (pintype "input"))
    )
    (net (code "43") (name "unconnected-(PO1-SSTXP1-PadA2)") (class "Default")
      (node (ref "PO1") (pin "A2") (pinfunction "SSTXP1_A2") (pintype "input"))
    )
    (net (code "44") (name "unconnected-(PO1-SSTXn1-PadA3)") (class "Default")
      (node (ref "PO1") (pin "A3") (pinfunction "SSTXn1_A3") (pintype "input"))
    )
    (net (code "45") (name "unconnected-(PO1-SSTXn2-PadB3)") (class "Default")
      (node (ref "PO1") (pin "B3") (pinfunction "SSTXn2_B3") (pintype "input"))
    )
    (net (code "46") (name "unconnected-(PO1-SSTXp2-PadB2)") (class "Default")
      (node (ref "PO1") (pin "B2") (pinfunction "SSTXp2_B2") (pintype "input"))
    )
    (net (code "47") (name "unconnected-(PO1-SUB1-PadA8)") (class "Default")
      (node (ref "PO1") (pin "A8") (pinfunction "SUB1_A8") (pintype "input"))
    )
    (net (code "48") (name "unconnected-(PO1-SUB2-PadB8)") (class "Default")
      (node (ref "PO1") (pin "B8") (pinfunction "SUB2_B8") (pintype "input"))
    )
    (net (code "49") (name "unconnected-(PO2-DN1-PadA7)") (class "Default")
      (node (ref "PO2") (pin "A7") (pinfunction "DN1_A7") (pintype "input"))
    )
    (net (code "50") (name "unconnected-(PO2-DN2-PadB7)") (class "Default")
      (node (ref "PO2") (pin "B7") (pinfunction "DN2_B7") (pintype "input"))
    )
    (net (code "51") (name "unconnected-(PO2-DP1-PadA6)") (class "Default")
      (node (ref "PO2") (pin "A6") (pinfunction "DP1_A6") (pintype "input"))
    )
    (net (code "52") (name "unconnected-(PO2-DP2-PadB6)") (class "Default")
      (node (ref "PO2") (pin "B6") (pinfunction "DP2_B6") (pintype "input"))
    )
    (net (code "53") (name "unconnected-(PO2-SSRXn1-PadB10)") (class "Default")
      (node (ref "PO2") (pin "B10") (pinfunction "SSRXn1_B10") (pintype "input"))
    )
    (net (code "54") (name "unconnected-(PO2-SSRXn2-PadA10)") (class "Default")
      (node (ref "PO2") (pin "A10") (pinfunction "SSRXn2_A10") (pintype "input"))
    )
    (net (code "55") (name "unconnected-(PO2-SSRXp1-PadB11)") (class "Default")
      (node (ref "PO2") (pin "B11") (pinfunction "SSRXp1_B11") (pintype "input"))
    )
    (net (code "56") (name "unconnected-(PO2-SSRXp2-PadA11)") (class "Default")
      (node (ref "PO2") (pin "A11") (pinfunction "SSRXp2_A11") (pintype "input"))
    )
    (net (code "57") (name "unconnected-(PO2-SSTXP1-PadA2)") (class "Default")
      (node (ref "PO2") (pin "A2") (pinfunction "SSTXP1_A2") (pintype "input"))
    )
    (net (code "58") (name "unconnected-(PO2-SSTXn1-PadA3)") (class "Default")
      (node (ref "PO2") (pin "A3") (pinfunction "SSTXn1_A3") (pintype "input"))
    )
    (net (code "59") (name "unconnected-(PO2-SSTXn2-PadB3)") (class "Default")
      (node (ref "PO2") (pin "B3") (pinfunction "SSTXn2_B3") (pintype "input"))
    )
    (net (code "60") (name "unconnected-(PO2-SSTXp2-PadB2)") (class "Default")
      (node (ref "PO2") (pin "B2") (pinfunction "SSTXp2_B2") (pintype "input"))
    )
    (net (code "61") (name "unconnected-(PO2-SUB1-PadA8)") (class "Default")
      (node (ref "PO2") (pin "A8") (pinfunction "SUB1_A8") (pintype "input"))
    )
    (net (code "62") (name "unconnected-(PO2-SUB2-PadB8)") (class "Default")
      (node (ref "PO2") (pin "B8") (pinfunction "SUB2_B8") (pintype "input"))
    )
    (net (code "63") (name "unconnected-(PO3-DN1-PadA7)") (class "Default")
      (node (ref "PO3") (pin "A7") (pinfunction "DN1_A7") (pintype "input"))
    )
    (net (code "64") (name "unconnected-(PO3-DN2-PadB7)") (class "Default")
      (node (ref "PO3") (pin "B7") (pinfunction "DN2_B7") (pintype "input"))
    )
    (net (code "65") (name "unconnected-(PO3-DP1-PadA6)") (class "Default")
      (node (ref "PO3") (pin "A6") (pinfunction "DP1_A6") (pintype "input"))
    )
    (net (code "66") (name "unconnected-(PO3-DP2-PadB6)") (class "Default")
      (node (ref "PO3") (pin "B6") (pinfunction "DP2_B6") (pintype "input"))
    )
    (net (code "67") (name "unconnected-(PO3-SSRXn1-PadB10)") (class "Default")
      (node (ref "PO3") (pin "B10") (pinfunction "SSRXn1_B10") (pintype "input"))
    )
    (net (code "68") (name "unconnected-(PO3-SSRXn2-PadA10)") (class "Default")
      (node (ref "PO3") (pin "A10") (pinfunction "SSRXn2_A10") (pintype "input"))
    )
    (net (code "69") (name "unconnected-(PO3-SSRXp1-PadB11)") (class "Default")
      (node (ref "PO3") (pin "B11") (pinfunction "SSRXp1_B11") (pintype "input"))
    )
    (net (code "70") (name "unconnected-(PO3-SSRXp2-PadA11)") (class "Default")
      (node (ref "PO3") (pin "A11") (pinfunction "SSRXp2_A11") (pintype "input"))
    )
    (net (code "71") (name "unconnected-(PO3-SSTXP1-PadA2)") (class "Default")
      (node (ref "PO3") (pin "A2") (pinfunction "SSTXP1_A2") (pintype "input"))
    )
    (net (code "72") (name "unconnected-(PO3-SSTXn1-PadA3)") (class "Default")
      (node (ref "PO3") (pin "A3") (pinfunction "SSTXn1_A3") (pintype "input"))
    )
    (net (code "73") (name "unconnected-(PO3-SSTXn2-PadB3)") (class "Default")
      (node (ref "PO3") (pin "B3") (pinfunction "SSTXn2_B3") (pintype "input"))
    )
    (net (code "74") (name "unconnected-(PO3-SSTXp2-PadB2)") (class "Default")
      (node (ref "PO3") (pin "B2") (pinfunction "SSTXp2_B2") (pintype "input"))
    )
    (net (code "75") (name "unconnected-(PO3-SUB1-PadA8)") (class "Default")
      (node (ref "PO3") (pin "A8") (pinfunction "SUB1_A8") (pintype "input"))
    )
    (net (code "76") (name "unconnected-(PO3-SUB2-PadB8)") (class "Default")
      (node (ref "PO3") (pin "B8") (pinfunction "SUB2_B8") (pintype "input"))
    )
    (net (code "77") (name "unconnected-(PO4-DN1-PadA7)") (class "Default")
      (node (ref "PO4") (pin "A7") (pinfunction "DN1_A7") (pintype "input"))
    )
    (net (code "78") (name "unconnected-(PO4-DN2-PadB7)") (class "Default")
      (node (ref "PO4") (pin "B7") (pinfunction "DN2_B7") (pintype "input"))
    )
    (net (code "79") (name "unconnected-(PO4-DP1-PadA6)") (class "Default")
      (node (ref "PO4") (pin "A6") (pinfunction "DP1_A6") (pintype "input"))
    )
    (net (code "80") (name "unconnected-(PO4-DP2-PadB6)") (class "Default")
      (node (ref "PO4") (pin "B6") (pinfunction "DP2_B6") (pintype "input"))
    )
    (net (code "81") (name "unconnected-(PO4-SSRXn1-PadB10)") (class "Default")
      (node (ref "PO4") (pin "B10") (pinfunction "SSRXn1_B10") (pintype "input"))
    )
    (net (code "82") (name "unconnected-(PO4-SSRXn2-PadA10)") (class "Default")
      (node (ref "PO4") (pin "A10") (pinfunction "SSRXn2_A10") (pintype "input"))
    )
    (net (code "83") (name "unconnected-(PO4-SSRXp1-PadB11)") (class "Default")
      (node (ref "PO4") (pin "B11") (pinfunction "SSRXp1_B11") (pintype "input"))
    )
    (net (code "84") (name "unconnected-(PO4-SSRXp2-PadA11)") (class "Default")
      (node (ref "PO4") (pin "A11") (pinfunction "SSRXp2_A11") (pintype "input"))
    )
    (net (code "85") (name "unconnected-(PO4-SSTXP1-PadA2)") (class "Default")
      (node (ref "PO4") (pin "A2") (pinfunction "SSTXP1_A2") (pintype "input"))
    )
    (net (code "86") (name "unconnected-(PO4-SSTXn1-PadA3)") (class "Default")
      (node (ref "PO4") (pin "A3") (pinfunction "SSTXn1_A3") (pintype "input"))
    )
    (net (code "87") (name "unconnected-(PO4-SSTXn2-PadB3)") (class "Default")
      (node (ref "PO4") (pin "B3") (pinfunction "SSTXn2_B3") (pintype "input"))
    )
    (net (code "88") (name "unconnected-(PO4-SSTXp2-PadB2)") (class "Default")
      (node (ref "PO4") (pin "B2") (pinfunction "SSTXp2_B2") (pintype "input"))
    )
    (net (code "89") (name "unconnected-(PO4-SUB1-PadA8)") (class "Default")
      (node (ref "PO4") (pin "A8") (pinfunction "SUB1_A8") (pintype "input"))
    )
    (net (code "90") (name "unconnected-(PO4-SUB2-PadB8)") (class "Default")
      (node (ref "PO4") (pin "B8") (pinfunction "SUB2_B8") (pintype "input"))
    )
    (net (code "91") (name "unconnected-(PO5-DN1-PadA7)") (class "Default")
      (node (ref "PO5") (pin "A7") (pinfunction "DN1_A7") (pintype "input"))
    )
    (net (code "92") (name "unconnected-(PO5-DN2-PadB7)") (class "Default")
      (node (ref "PO5") (pin "B7") (pinfunction "DN2_B7") (pintype "input"))
    )
    (net (code "93") (name "unconnected-(PO5-DP1-PadA6)") (class "Default")
      (node (ref "PO5") (pin "A6") (pinfunction "DP1_A6") (pintype "input"))
    )
    (net (code "94") (name "unconnected-(PO5-DP2-PadB6)") (class "Default")
      (node (ref "PO5") (pin "B6") (pinfunction "DP2_B6") (pintype "input"))
    )
    (net (code "95") (name "unconnected-(PO5-SSRXn1-PadB10)") (class "Default")
      (node (ref "PO5") (pin "B10") (pinfunction "SSRXn1_B10") (pintype "input"))
    )
    (net (code "96") (name "unconnected-(PO5-SSRXn2-PadA10)") (class "Default")
      (node (ref "PO5") (pin "A10") (pinfunction "SSRXn2_A10") (pintype "input"))
    )
    (net (code "97") (name "unconnected-(PO5-SSRXp1-PadB11)") (class "Default")
      (node (ref "PO5") (pin "B11") (pinfunction "SSRXp1_B11") (pintype "input"))
    )
    (net (code "98") (name "unconnected-(PO5-SSRXp2-PadA11)") (class "Default")
      (node (ref "PO5") (pin "A11") (pinfunction "SSRXp2_A11") (pintype "input"))
    )
    (net (code "99") (name "unconnected-(PO5-SSTXP1-PadA2)") (class "Default")
      (node (ref "PO5") (pin "A2") (pinfunction "SSTXP1_A2") (pintype "input"))
    )
    (net (code "100") (name "unconnected-(PO5-SSTXn1-PadA3)") (class "Default")
      (node (ref "PO5") (pin "A3") (pinfunction "SSTXn1_A3") (pintype "input"))
    )
    (net (code "101") (name "unconnected-(PO5-SSTXn2-PadB3)") (class "Default")
      (node (ref "PO5") (pin "B3") (pinfunction "SSTXn2_B3") (pintype "input"))
    )
    (net (code "102") (name "unconnected-(PO5-SSTXp2-PadB2)") (class "Default")
      (node (ref "PO5") (pin "B2") (pinfunction "SSTXp2_B2") (pintype "input"))
    )
    (net (code "103") (name "unconnected-(PO5-SUB1-PadA8)") (class "Default")
      (node (ref "PO5") (pin "A8") (pinfunction "SUB1_A8") (pintype "input"))
    )
    (net (code "104") (name "unconnected-(PO5-SUB2-PadB8)") (class "Default")
      (node (ref "PO5") (pin "B8") (pinfunction "SUB2_B8") (pintype "input"))
    )
    (net (code "105") (name "unconnected-(PO6-DN1-PadA7)") (class "Default")
      (node (ref "PO6") (pin "A7") (pinfunction "DN1_A7") (pintype "input"))
    )
    (net (code "106") (name "unconnected-(PO6-DN2-PadB7)") (class "Default")
      (node (ref "PO6") (pin "B7") (pinfunction "DN2_B7") (pintype "input"))
    )
    (net (code "107") (name "unconnected-(PO6-DP1-PadA6)") (class "Default")
      (node (ref "PO6") (pin "A6") (pinfunction "DP1_A6") (pintype "input"))
    )
    (net (code "108") (name "unconnected-(PO6-DP2-PadB6)") (class "Default")
      (node (ref "PO6") (pin "B6") (pinfunction "DP2_B6") (pintype "input"))
    )
    (net (code "109") (name "unconnected-(PO6-SSRXn1-PadB10)") (class "Default")
      (node (ref "PO6") (pin "B10") (pinfunction "SSRXn1_B10") (pintype "input"))
    )
    (net (code "110") (name "unconnected-(PO6-SSRXn2-PadA10)") (class "Default")
      (node (ref "PO6") (pin "A10") (pinfunction "SSRXn2_A10") (pintype "input"))
    )
    (net (code "111") (name "unconnected-(PO6-SSRXp1-PadB11)") (class "Default")
      (node (ref "PO6") (pin "B11") (pinfunction "SSRXp1_B11") (pintype "input"))
    )
    (net (code "112") (name "unconnected-(PO6-SSRXp2-PadA11)") (class "Default")
      (node (ref "PO6") (pin "A11") (pinfunction "SSRXp2_A11") (pintype "input"))
    )
    (net (code "113") (name "unconnected-(PO6-SSTXP1-PadA2)") (class "Default")
      (node (ref "PO6") (pin "A2") (pinfunction "SSTXP1_A2") (pintype "input"))
    )
    (net (code "114") (name "unconnected-(PO6-SSTXn1-PadA3)") (class "Default")
      (node (ref "PO6") (pin "A3") (pinfunction "SSTXn1_A3") (pintype "input"))
    )
    (net (code "115") (name "unconnected-(PO6-SSTXn2-PadB3)") (class "Default")
      (node (ref "PO6") (pin "B3") (pinfunction "SSTXn2_B3") (pintype "input"))
    )
    (net (code "116") (name "unconnected-(PO6-SSTXp2-PadB2)") (class "Default")
      (node (ref "PO6") (pin "B2") (pinfunction "SSTXp2_B2") (pintype "input"))
    )
    (net (code "117") (name "unconnected-(PO6-SUB1-PadA8)") (class "Default")
      (node (ref "PO6") (pin "A8") (pinfunction "SUB1_A8") (pintype "input"))
    )
    (net (code "118") (name "unconnected-(PO6-SUB2-PadB8)") (class "Default")
      (node (ref "PO6") (pin "B8") (pinfunction "SUB2_B8") (pintype "input"))
    )
    (net (code "119") (name "unconnected-(PO7-DN1-PadA7)") (class "Default")
      (node (ref "PO7") (pin "A7") (pinfunction "DN1_A7") (pintype "input"))
    )
    (net (code "120") (name "unconnected-(PO7-DN2-PadB7)") (class "Default")
      (node (ref "PO7") (pin "B7") (pinfunction "DN2_B7") (pintype "input"))
    )
    (net (code "121") (name "unconnected-(PO7-DP1-PadA6)") (class "Default")
      (node (ref "PO7") (pin "A6") (pinfunction "DP1_A6") (pintype "input"))
    )
    (net (code "122") (name "unconnected-(PO7-DP2-PadB6)") (class "Default")
      (node (ref "PO7") (pin "B6") (pinfunction "DP2_B6") (pintype "input"))
    )
    (net (code "123") (name "unconnected-(PO7-SSRXn1-PadB10)") (class "Default")
      (node (ref "PO7") (pin "B10") (pinfunction "SSRXn1_B10") (pintype "input"))
    )
    (net (code "124") (name "unconnected-(PO7-SSRXn2-PadA10)") (class "Default")
      (node (ref "PO7") (pin "A10") (pinfunction "SSRXn2_A10") (pintype "input"))
    )
    (net (code "125") (name "unconnected-(PO7-SSRXp1-PadB11)") (class "Default")
      (node (ref "PO7") (pin "B11") (pinfunction "SSRXp1_B11") (pintype "input"))
    )
    (net (code "126") (name "unconnected-(PO7-SSRXp2-PadA11)") (class "Default")
      (node (ref "PO7") (pin "A11") (pinfunction "SSRXp2_A11") (pintype "input"))
    )
    (net (code "127") (name "unconnected-(PO7-SSTXP1-PadA2)") (class "Default")
      (node (ref "PO7") (pin "A2") (pinfunction "SSTXP1_A2") (pintype "input"))
    )
    (net (code "128") (name "unconnected-(PO7-SSTXn1-PadA3)") (class "Default")
      (node (ref "PO7") (pin "A3") (pinfunction "SSTXn1_A3") (pintype "input"))
    )
    (net (code "129") (name "unconnected-(PO7-SSTXn2-PadB3)") (class "Default")
      (node (ref "PO7") (pin "B3") (pinfunction "SSTXn2_B3") (pintype "input"))
    )
    (net (code "130") (name "unconnected-(PO7-SSTXp2-PadB2)") (class "Default")
      (node (ref "PO7") (pin "B2") (pinfunction "SSTXp2_B2") (pintype "input"))
    )
    (net (code "131") (name "unconnected-(PO7-SUB1-PadA8)") (class "Default")
      (node (ref "PO7") (pin "A8") (pinfunction "SUB1_A8") (pintype "input"))
    )
    (net (code "132") (name "unconnected-(PO7-SUB2-PadB8)") (class "Default")
      (node (ref "PO7") (pin "B8") (pinfunction "SUB2_B8") (pintype "input"))
    )
    (net (code "133") (name "unconnected-(PO8-DN1-PadA7)") (class "Default")
      (node (ref "PO8") (pin "A7") (pinfunction "DN1_A7") (pintype "input"))
    )
    (net (code "134") (name "unconnected-(PO8-DN2-PadB7)") (class "Default")
      (node (ref "PO8") (pin "B7") (pinfunction "DN2_B7") (pintype "input"))
    )
    (net (code "135") (name "unconnected-(PO8-DP1-PadA6)") (class "Default")
      (node (ref "PO8") (pin "A6") (pinfunction "DP1_A6") (pintype "input"))
    )
    (net (code "136") (name "unconnected-(PO8-DP2-PadB6)") (class "Default")
      (node (ref "PO8") (pin "B6") (pinfunction "DP2_B6") (pintype "input"))
    )
    (net (code "137") (name "unconnected-(PO8-SSRXn1-PadB10)") (class "Default")
      (node (ref "PO8") (pin "B10") (pinfunction "SSRXn1_B10") (pintype "input"))
    )
    (net (code "138") (name "unconnected-(PO8-SSRXn2-PadA10)") (class "Default")
      (node (ref "PO8") (pin "A10") (pinfunction "SSRXn2_A10") (pintype "input"))
    )
    (net (code "139") (name "unconnected-(PO8-SSRXp1-PadB11)") (class "Default")
      (node (ref "PO8") (pin "B11") (pinfunction "SSRXp1_B11") (pintype "input"))
    )
    (net (code "140") (name "unconnected-(PO8-SSRXp2-PadA11)") (class "Default")
      (node (ref "PO8") (pin "A11") (pinfunction "SSRXp2_A11") (pintype "input"))
    )
    (net (code "141") (name "unconnected-(PO8-SSTXP1-PadA2)") (class "Default")
      (node (ref "PO8") (pin "A2") (pinfunction "SSTXP1_A2") (pintype "input"))
    )
    (net (code "142") (name "unconnected-(PO8-SSTXn1-PadA3)") (class "Default")
      (node (ref "PO8") (pin "A3") (pinfunction "SSTXn1_A3") (pintype "input"))
    )
    (net (code "143") (name "unconnected-(PO8-SSTXn2-PadB3)") (class "Default")
      (node (ref "PO8") (pin "B3") (pinfunction "SSTXn2_B3") (pintype "input"))
    )
    (net (code "144") (name "unconnected-(PO8-SSTXp2-PadB2)") (class "Default")
      (node (ref "PO8") (pin "B2") (pinfunction "SSTXp2_B2") (pintype "input"))
    )
    (net (code "145") (name "unconnected-(PO8-SUB1-PadA8)") (class "Default")
      (node (ref "PO8") (pin "A8") (pinfunction "SUB1_A8") (pintype "input"))
    )
    (net (code "146") (name "unconnected-(PO8-SUB2-PadB8)") (class "Default")
      (node (ref "PO8") (pin "B8") (pinfunction "SUB2_B8") (pintype "input"))
    )
    (net (code "147") (name "unconnected-(PO9-DN1-PadA7)") (class "Default")
      (node (ref "PO9") (pin "A7") (pinfunction "DN1_A7") (pintype "input"))
    )
    (net (code "148") (name "unconnected-(PO9-DN2-PadB7)") (class "Default")
      (node (ref "PO9") (pin "B7") (pinfunction "DN2_B7") (pintype "input"))
    )
    (net (code "149") (name "unconnected-(PO9-DP1-PadA6)") (class "Default")
      (node (ref "PO9") (pin "A6") (pinfunction "DP1_A6") (pintype "input"))
    )
    (net (code "150") (name "unconnected-(PO9-DP2-PadB6)") (class "Default")
      (node (ref "PO9") (pin "B6") (pinfunction "DP2_B6") (pintype "input"))
    )
    (net (code "151") (name "unconnected-(PO9-SSRXn1-PadB10)") (class "Default")
      (node (ref "PO9") (pin "B10") (pinfunction "SSRXn1_B10") (pintype "input"))
    )
    (net (code "152") (name "unconnected-(PO9-SSRXn2-PadA10)") (class "Default")
      (node (ref "PO9") (pin "A10") (pinfunction "SSRXn2_A10") (pintype "input"))
    )
    (net (code "153") (name "unconnected-(PO9-SSRXp1-PadB11)") (class "Default")
      (node (ref "PO9") (pin "B11") (pinfunction "SSRXp1_B11") (pintype "input"))
    )
    (net (code "154") (name "unconnected-(PO9-SSRXp2-PadA11)") (class "Default")
      (node (ref "PO9") (pin "A11") (pinfunction "SSRXp2_A11") (pintype "input"))
    )
    (net (code "155") (name "unconnected-(PO9-SSTXP1-PadA2)") (class "Default")
      (node (ref "PO9") (pin "A2") (pinfunction "SSTXP1_A2") (pintype "input"))
    )
    (net (code "156") (name "unconnected-(PO9-SSTXn1-PadA3)") (class "Default")
      (node (ref "PO9") (pin "A3") (pinfunction "SSTXn1_A3") (pintype "input"))
    )
    (net (code "157") (name "unconnected-(PO9-SSTXn2-PadB3)") (class "Default")
      (node (ref "PO9") (pin "B3") (pinfunction "SSTXn2_B3") (pintype "input"))
    )
    (net (code "158") (name "unconnected-(PO9-SSTXp2-PadB2)") (class "Default")
      (node (ref "PO9") (pin "B2") (pinfunction "SSTXp2_B2") (pintype "input"))
    )
    (net (code "159") (name "unconnected-(PO9-SUB1-PadA8)") (class "Default")
      (node (ref "PO9") (pin "A8") (pinfunction "SUB1_A8") (pintype "input"))
    )
    (net (code "160") (name "unconnected-(PO9-SUB2-PadB8)") (class "Default")
      (node (ref "PO9") (pin "B8") (pinfunction "SUB2_B8") (pintype "input"))
    )
    (net (code "161") (name "unconnected-(PO10-DN1-PadA7)") (class "Default")
      (node (ref "PO10") (pin "A7") (pinfunction "DN1_A7") (pintype "input"))
    )
    (net (code "162") (name "unconnected-(PO10-DN2-PadB7)") (class "Default")
      (node (ref "PO10") (pin "B7") (pinfunction "DN2_B7") (pintype "input"))
    )
    (net (code "163") (name "unconnected-(PO10-DP1-PadA6)") (class "Default")
      (node (ref "PO10") (pin "A6") (pinfunction "DP1_A6") (pintype "input"))
    )
    (net (code "164") (name "unconnected-(PO10-DP2-PadB6)") (class "Default")
      (node (ref "PO10") (pin "B6") (pinfunction "DP2_B6") (pintype "input"))
    )
    (net (code "165") (name "unconnected-(PO10-SSRXn1-PadB10)") (class "Default")
      (node (ref "PO10") (pin "B10") (pinfunction "SSRXn1_B10") (pintype "input"))
    )
    (net (code "166") (name "unconnected-(PO10-SSRXn2-PadA10)") (class "Default")
      (node (ref "PO10") (pin "A10") (pinfunction "SSRXn2_A10") (pintype "input"))
    )
    (net (code "167") (name "unconnected-(PO10-SSRXp1-PadB11)") (class "Default")
      (node (ref "PO10") (pin "B11") (pinfunction "SSRXp1_B11") (pintype "input"))
    )
    (net (code "168") (name "unconnected-(PO10-SSRXp2-PadA11)") (class "Default")
      (node (ref "PO10") (pin "A11") (pinfunction "SSRXp2_A11") (pintype "input"))
    )
    (net (code "169") (name "unconnected-(PO10-SSTXP1-PadA2)") (class "Default")
      (node (ref "PO10") (pin "A2") (pinfunction "SSTXP1_A2") (pintype "input"))
    )
    (net (code "170") (name "unconnected-(PO10-SSTXn1-PadA3)") (class "Default")
      (node (ref "PO10") (pin "A3") (pinfunction "SSTXn1_A3") (pintype "input"))
    )
    (net (code "171") (name "unconnected-(PO10-SSTXn2-PadB3)") (class "Default")
      (node (ref "PO10") (pin "B3") (pinfunction "SSTXn2_B3") (pintype "input"))
    )
    (net (code "172") (name "unconnected-(PO10-SSTXp2-PadB2)") (class "Default")
      (node (ref "PO10") (pin "B2") (pinfunction "SSTXp2_B2") (pintype "input"))
    )
    (net (code "173") (name "unconnected-(PO10-SUB1-PadA8)") (class "Default")
      (node (ref "PO10") (pin "A8") (pinfunction "SUB1_A8") (pintype "input"))
    )
    (net (code "174") (name "unconnected-(PO10-SUB2-PadB8)") (class "Default")
      (node (ref "PO10") (pin "B8") (pinfunction "SUB2_B8") (pintype "input"))
    )
    (net (code "175") (name "unconnected-(USB1-SBU1-PadA8)") (class "Default")
      (node (ref "USB1") (pin "A8") (pinfunction "SBU1_A8") (pintype "unspecified+no_connect"))
    )
    (net (code "176") (name "unconnected-(USB1-SBU2-PadB8)") (class "Default")
      (node (ref "USB1") (pin "B8") (pinfunction "SBU2_B8") (pintype "unspecified+no_connect"))
    )
  )
)
